# design.net
KiCad netlist of a schematic drawn in Altium Designer
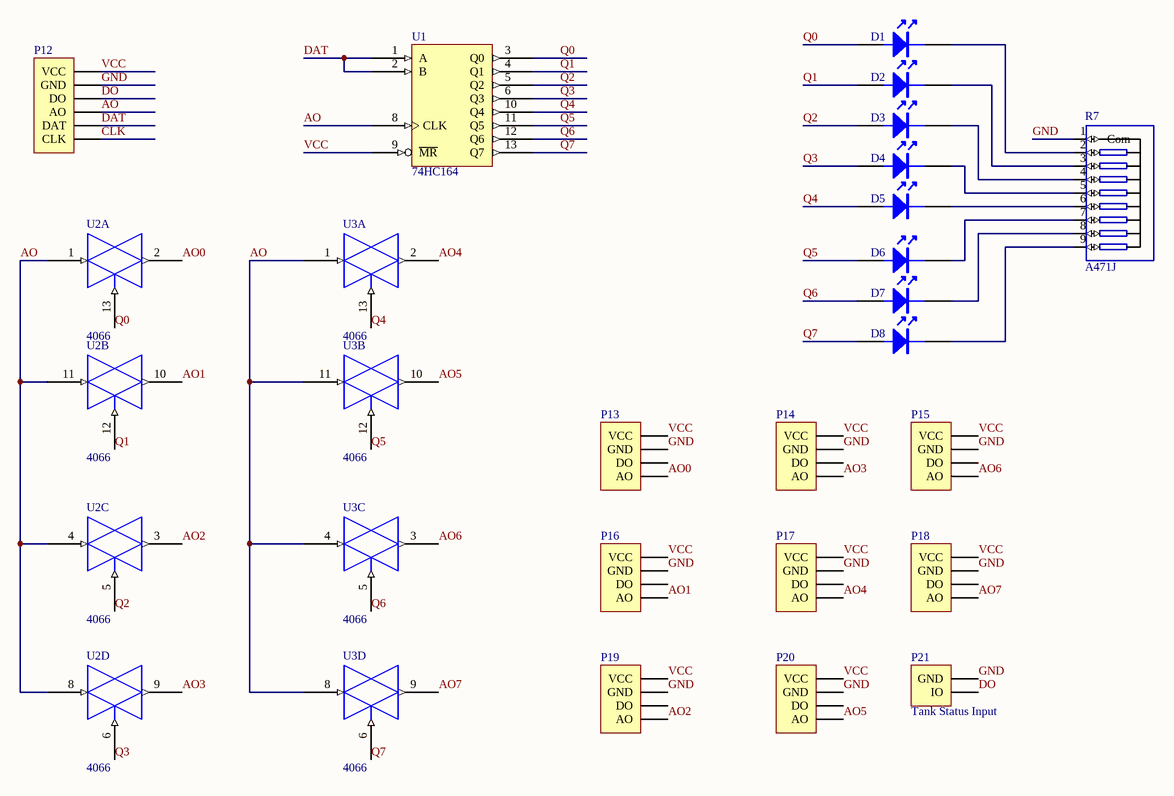
[diagram p0: 扩展板.SchDoc]

(export (version "E")
  (design (tool "Eeschema 10.0.6"))
  (components
    (comp (ref "D1") (value "~") (footprint "DIODE0.4A") (libsource (lib "二极管") (part "发光二极管")))
    (comp (ref "D2") (value "~") (footprint "DIODE0.4A") (libsource (lib "二极管") (part "发光二极管")))
    (comp (ref "D3") (value "~") (footprint "DIODE0.4A") (libsource (lib "二极管") (part "发光二极管")))
    (comp (ref "D4") (value "~") (footprint "DIODE0.4A") (libsource (lib "二极管") (part "发光二极管")))
    (comp (ref "D5") (value "~") (footprint "DIODE0.4A") (libsource (lib "二极管") (part "发光二极管")))
    (comp (ref "D6") (value "~") (footprint "DIODE0.4A") (libsource (lib "二极管") (part "发光二极管")))
    (comp (ref "D7") (value "~") (footprint "DIODE0.4A") (libsource (lib "二极管") (part "发光二极管")))
    (comp (ref "D8") (value "~") (footprint "DIODE0.4A") (libsource (lib "二极管") (part "发光二极管")))
    (comp (ref "P12")
      (value "~")
      (footprint "HDR1X6")
      (description "Header, 6-Pin")
      (fields (field (name "PUBLISHER") "Altium Limited"))
      (libsource (lib "Miscellaneous Connectors") (part "Header 6"))
    )
    (comp (ref "P13")
      (value "~")
      (footprint "HDR1X4")
      (description "Header, 4-Pin")
      (fields (field (name "PUBLISHER") "Altium Limited"))
      (libsource (lib "Miscellaneous Connectors") (part "Header 4"))
    )
    (comp (ref "P14")
      (value "~")
      (footprint "HDR1X4")
      (description "Header, 4-Pin")
      (fields (field (name "PUBLISHER") "Altium Limited"))
      (libsource (lib "Miscellaneous Connectors") (part "Header 4"))
    )
    (comp (ref "P15")
      (value "~")
      (footprint "HDR1X4")
      (description "Header, 4-Pin")
      (fields (field (name "PUBLISHER") "Altium Limited"))
      (libsource (lib "Miscellaneous Connectors") (part "Header 4"))
    )
    (comp (ref "P16")
      (value "~")
      (footprint "HDR1X4")
      (description "Header, 4-Pin")
      (fields (field (name "PUBLISHER") "Altium Limited"))
      (libsource (lib "Miscellaneous Connectors") (part "Header 4"))
    )
    (comp (ref "P17")
      (value "~")
      (footprint "HDR1X4")
      (description "Header, 4-Pin")
      (fields (field (name "PUBLISHER") "Altium Limited"))
      (libsource (lib "Miscellaneous Connectors") (part "Header 4"))
    )
    (comp (ref "P18")
      (value "~")
      (footprint "HDR1X4")
      (description "Header, 4-Pin")
      (fields (field (name "PUBLISHER") "Altium Limited"))
      (libsource (lib "Miscellaneous Connectors") (part "Header 4"))
    )
    (comp (ref "P19")
      (value "~")
      (footprint "HDR1X4")
      (description "Header, 4-Pin")
      (fields (field (name "PUBLISHER") "Altium Limited"))
      (libsource (lib "Miscellaneous Connectors") (part "Header 4"))
    )
    (comp (ref "P20")
      (value "~")
      (footprint "HDR1X4")
      (description "Header, 4-Pin")
      (fields (field (name "PUBLISHER") "Altium Limited"))
      (libsource (lib "Miscellaneous Connectors") (part "Header 4"))
    )
    (comp (ref "P21")
      (value "Tank Status Input")
      (footprint "HDR1X2")
      (description "Header, 2-Pin")
      (fields (field (name "PUBLISHER") "Altium Limited"))
      (libsource (lib "Miscellaneous Connectors") (part "Header 2"))
    )
    (comp (ref "R7") (value "A471J") (footprint "SIP9") (libsource (lib "电阻") (part "RES10")))
    (comp (ref "U1") (value "74HC164") (footprint "DIP-14") (libsource (lib "TTL74系列IC") (part "74HC164")))
    (comp (ref "U2") (value "4066") (footprint "DIP-14") (libsource (lib "CD4000系列IC") (part "4066")))
    (comp (ref "U3") (value "4066") (footprint "DIP-14") (libsource (lib "CD4000系列IC") (part "4066")))
  )
  (nets
    (net (code "1") (name "/AO") (class "Default")
      (node (ref "P12") (pin "4") (pinfunction "AO_4") (pintype "passive"))
      (node (ref "U1") (pin "8") (pinfunction "CLK_8") (pintype "input"))
      (node (ref "U2") (pin "1") (pintype "input"))
      (node (ref "U2") (pin "11") (pintype "input"))
      (node (ref "U2") (pin "4") (pintype "input"))
      (node (ref "U2") (pin "8") (pintype "input"))
      (node (ref "U3") (pin "1") (pintype "input"))
      (node (ref "U3") (pin "11") (pintype "input"))
      (node (ref "U3") (pin "4") (pintype "input"))
      (node (ref "U3") (pin "8") (pintype "input"))
    )
    (net (code "2") (name "/AO0") (class "Default")
      (node (ref "P13") (pin "4") (pinfunction "AO_4") (pintype "passive"))
      (node (ref "U2") (pin "2") (pintype "output"))
    )
    (net (code "3") (name "/AO1") (class "Default")
      (node (ref "P16") (pin "4") (pinfunction "AO_4") (pintype "passive"))
      (node (ref "U2") (pin "10") (pintype "output"))
    )
    (net (code "4") (name "/AO2") (class "Default")
      (node (ref "P19") (pin "4") (pinfunction "AO_4") (pintype "passive"))
      (node (ref "U2") (pin "3") (pintype "output"))
    )
    (net (code "5") (name "/AO3") (class "Default")
      (node (ref "P14") (pin "4") (pinfunction "AO_4") (pintype "passive"))
      (node (ref "U2") (pin "9") (pintype "output"))
    )
    (net (code "6") (name "/AO4") (class "Default")
      (node (ref "P17") (pin "4") (pinfunction "AO_4") (pintype "passive"))
      (node (ref "U3") (pin "2") (pintype "output"))
    )
    (net (code "7") (name "/AO5") (class "Default")
      (node (ref "P20") (pin "4") (pinfunction "AO_4") (pintype "passive"))
      (node (ref "U3") (pin "10") (pintype "output"))
    )
    (net (code "8") (name "/AO6") (class "Default")
      (node (ref "P15") (pin "4") (pinfunction "AO_4") (pintype "passive"))
      (node (ref "U3") (pin "3") (pintype "output"))
    )
    (net (code "9") (name "/AO7") (class "Default")
      (node (ref "P18") (pin "4") (pinfunction "AO_4") (pintype "passive"))
      (node (ref "U3") (pin "9") (pintype "output"))
    )
    (net (code "10") (name "/CLK") (class "Default")
      (node (ref "P12") (pin "6") (pinfunction "CLK_6") (pintype "passive"))
    )
    (net (code "11") (name "/DAT") (class "Default")
      (node (ref "P12") (pin "5") (pinfunction "DAT_5") (pintype "passive"))
      (node (ref "U1") (pin "1") (pinfunction "A_1") (pintype "input"))
      (node (ref "U1") (pin "2") (pinfunction "B_2") (pintype "input"))
    )
    (net (code "12") (name "/DO") (class "Default")
      (node (ref "P12") (pin "3") (pinfunction "DO_3") (pintype "passive"))
      (node (ref "P21") (pin "2") (pinfunction "IO_2") (pintype "passive"))
    )
    (net (code "13") (name "/Q0") (class "Default")
      (node (ref "D1") (pin "A") (pinfunction "1_A") (pintype "passive"))
      (node (ref "U1") (pin "3") (pinfunction "Q0_3") (pintype "output"))
      (node (ref "U2") (pin "13") (pintype "input"))
    )
    (net (code "14") (name "/Q1") (class "Default")
      (node (ref "D2") (pin "A") (pinfunction "1_A") (pintype "passive"))
      (node (ref "U1") (pin "4") (pinfunction "Q1_4") (pintype "output"))
      (node (ref "U2") (pin "12") (pintype "input"))
    )
    (net (code "15") (name "/Q2") (class "Default")
      (node (ref "D3") (pin "A") (pinfunction "1_A") (pintype "passive"))
      (node (ref "U1") (pin "5") (pinfunction "Q2_5") (pintype "output"))
      (node (ref "U2") (pin "5") (pintype "input"))
    )
    (net (code "16") (name "/Q3") (class "Default")
      (node (ref "D4") (pin "A") (pinfunction "1_A") (pintype "passive"))
      (node (ref "U1") (pin "6") (pinfunction "Q3_6") (pintype "output"))
      (node (ref "U2") (pin "6") (pintype "input"))
    )
    (net (code "17") (name "/Q4") (class "Default")
      (node (ref "D5") (pin "A") (pinfunction "1_A") (pintype "passive"))
      (node (ref "U1") (pin "10") (pinfunction "Q4_10") (pintype "output"))
      (node (ref "U3") (pin "13") (pintype "input"))
    )
    (net (code "18") (name "/Q5") (class "Default")
      (node (ref "D6") (pin "A") (pinfunction "1_A") (pintype "passive"))
      (node (ref "U1") (pin "11") (pinfunction "Q5_11") (pintype "output"))
      (node (ref "U3") (pin "12") (pintype "input"))
    )
    (net (code "19") (name "/Q6") (class "Default")
      (node (ref "D7") (pin "A") (pinfunction "1_A") (pintype "passive"))
      (node (ref "U1") (pin "12") (pinfunction "Q6_12") (pintype "output"))
      (node (ref "U3") (pin "5") (pintype "input"))
    )
    (net (code "20") (name "/Q7") (class "Default")
      (node (ref "D8") (pin "A") (pinfunction "1_A") (pintype "passive"))
      (node (ref "U1") (pin "13") (pinfunction "Q7_13") (pintype "output"))
      (node (ref "U3") (pin "6") (pintype "input"))
    )
    (net (code "21") (name "GND") (class "Default")
      (node (ref "P12") (pin "2") (pinfunction "GND_2") (pintype "passive"))
      (node (ref "P13") (pin "2") (pinfunction "GND_2") (pintype "passive"))
      (node (ref "P14") (pin "2") (pinfunction "GND_2") (pintype "passive"))
      (node (ref "P15") (pin "2") (pinfunction "GND_2") (pintype "passive"))
      (node (ref "P16") (pin "2") (pinfunction "GND_2") (pintype "passive"))
      (node (ref "P17") (pin "2") (pinfunction "GND_2") (pintype "passive"))
      (node (ref "P18") (pin "2") (pinfunction "GND_2") (pintype "passive"))
      (node (ref "P19") (pin "2") (pinfunction "GND_2") (pintype "passive"))
      (node (ref "P20") (pin "2") (pinfunction "GND_2") (pintype "passive"))
      (node (ref "P21") (pin "1") (pinfunction "GND_1") (pintype "passive"))
      (node (ref "R7") (pin "1") (pinfunction "Com_1") (pintype "bidirectional"))
      (node (ref "U1") (pin "7") (pinfunction "GND_7") (pintype "power_in"))
      (node (ref "U2") (pin "7") (pinfunction "GND_7") (pintype "power_in"))
      (node (ref "U3") (pin "7") (pinfunction "GND_7") (pintype "power_in"))
    )
    (net (code "22") (name "Net-(D1-2)") (class "Default")
      (node (ref "D1") (pin "K") (pinfunction "2_K") (pintype "passive"))
      (node (ref "R7") (pin "2") (pinfunction "2_2") (pintype "bidirectional"))
    )
    (net (code "23") (name "Net-(D2-2)") (class "Default")
      (node (ref "D2") (pin "K") (pinfunction "2_K") (pintype "passive"))
      (node (ref "R7") (pin "3") (pinfunction "3_3") (pintype "bidirectional"))
    )
    (net (code "24") (name "Net-(D3-2)") (class "Default")
      (node (ref "D3") (pin "K") (pinfunction "2_K") (pintype "passive"))
      (node (ref "R7") (pin "4") (pinfunction "4_4") (pintype "bidirectional"))
    )
    (net (code "25") (name "Net-(D4-2)") (class "Default")
      (node (ref "D4") (pin "K") (pinfunction "2_K") (pintype "passive"))
      (node (ref "R7") (pin "5") (pinfunction "5_5") (pintype "bidirectional"))
    )
    (net (code "26") (name "Net-(D5-2)") (class "Default")
      (node (ref "D5") (pin "K") (pinfunction "2_K") (pintype "passive"))
      (node (ref "R7") (pin "6") (pinfunction "6_6") (pintype "bidirectional"))
    )
    (net (code "27") (name "Net-(D6-2)") (class "Default")
      (node (ref "D6") (pin "K") (pinfunction "2_K") (pintype "passive"))
      (node (ref "R7") (pin "7") (pinfunction "7_7") (pintype "bidirectional"))
    )
    (net (code "28") (name "Net-(D7-2)") (class "Default")
      (node (ref "D7") (pin "K") (pinfunction "2_K") (pintype "passive"))
      (node (ref "R7") (pin "8") (pinfunction "8_8") (pintype "bidirectional"))
    )
    (net (code "29") (name "Net-(D8-2)") (class "Default")
      (node (ref "D8") (pin "K") (pinfunction "2_K") (pintype "passive"))
      (node (ref "R7") (pin "9") (pinfunction "9_9") (pintype "bidirectional"))
    )
    (net (code "30") (name "VCC") (class "Default")
      (node (ref "P12") (pin "1") (pinfunction "VCC_1") (pintype "passive"))
      (node (ref "P13") (pin "1") (pinfunction "VCC_1") (pintype "passive"))
      (node (ref "P14") (pin "1") (pinfunction "VCC_1") (pintype "passive"))
      (node (ref "P15") (pin "1") (pinfunction "VCC_1") (pintype "passive"))
      (node (ref "P16") (pin "1") (pinfunction "VCC_1") (pintype "passive"))
      (node (ref "P17") (pin "1") (pinfunction "VCC_1") (pintype "passive"))
      (node (ref "P18") (pin "1") (pinfunction "VCC_1") (pintype "passive"))
      (node (ref "P19") (pin "1") (pinfunction "VCC_1") (pintype "passive"))
      (node (ref "P20") (pin "1") (pinfunction "VCC_1") (pintype "passive"))
      (node (ref "U1") (pin "14") (pinfunction "VCC_14") (pintype "power_in"))
      (node (ref "U1") (pin "9") (pinfunction "~{MR}_9") (pintype "input"))
      (node (ref "U2") (pin "14") (pinfunction "VCC_14") (pintype "power_in"))
      (node (ref "U3") (pin "14") (pinfunction "VCC_14") (pintype "power_in"))
    )
    (net (code "31") (name "unconnected-(P13-DO-Pad3)") (class "Default")
      (node (ref "P13") (pin "3") (pinfunction "DO_3") (pintype "passive"))
    )
    (net (code "32") (name "unconnected-(P14-DO-Pad3)") (class "Default")
      (node (ref "P14") (pin "3") (pinfunction "DO_3") (pintype "passive"))
    )
    (net (code "33") (name "unconnected-(P15-DO-Pad3)") (class "Default")
      (node (ref "P15") (pin "3") (pinfunction "DO_3") (pintype "passive"))
    )
    (net (code "34") (name "unconnected-(P16-DO-Pad3)") (class "Default")
      (node (ref "P16") (pin "3") (pinfunction "DO_3") (pintype "passive"))
    )
    (net (code "35") (name "unconnected-(P17-DO-Pad3)") (class "Default")
      (node (ref "P17") (pin "3") (pinfunction "DO_3") (pintype "passive"))
    )
    (net (code "36") (name "unconnected-(P18-DO-Pad3)") (class "Default")
      (node (ref "P18") (pin "3") (pinfunction "DO_3") (pintype "passive"))
    )
    (net (code "37") (name "unconnected-(P19-DO-Pad3)") (class "Default")
      (node (ref "P19") (pin "3") (pinfunction "DO_3") (pintype "passive"))
    )
    (net (code "38") (name "unconnected-(P20-DO-Pad3)") (class "Default")
      (node (ref "P20") (pin "3") (pinfunction "DO_3") (pintype "passive"))
    )
  )
)
